# programmer.net
KiCad netlist of a schematic drawn in EAGLE
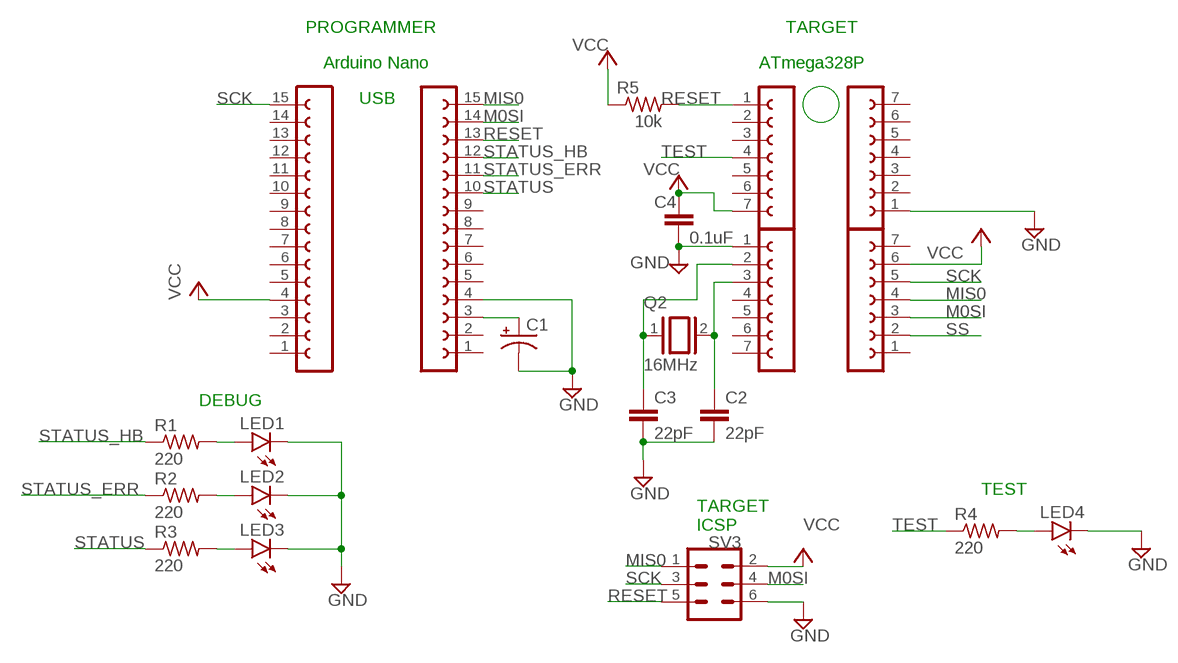
[diagram p0: schematic, sheet 1]

(export (version "E")
  (design (tool "Eeschema 10.0.6"))
  (components
    (comp (ref "C1")
      (value "CPOL-US153CLV-0405")
      (footprint "eagle-import:153CLV-0405")
      (libsource (lib "eagle-import") (part "CPOL-US153CLV-0405"))
    )
    (comp (ref "C2")
      (value "22pF")
      (footprint "eagle-import:C2.5-3")
      (libsource (lib "eagle-import") (part "C2,5-3"))
    )
    (comp (ref "C3")
      (value "22pF")
      (footprint "eagle-import:C2.5-3")
      (libsource (lib "eagle-import") (part "C2,5-3"))
    )
    (comp (ref "C4")
      (value "0.1uF")
      (footprint "eagle-import:C2.5-3")
      (libsource (lib "eagle-import") (part "C2,5-3"))
    )
    (comp (ref "LED1")
      (value "LED5MM")
      (footprint "eagle-import:LED5MM")
      (libsource (lib "eagle-import") (part "LED5MM"))
    )
    (comp (ref "LED2")
      (value "LED5MM")
      (footprint "eagle-import:LED5MM")
      (libsource (lib "eagle-import") (part "LED5MM"))
    )
    (comp (ref "LED3")
      (value "LED5MM")
      (footprint "eagle-import:LED5MM")
      (libsource (lib "eagle-import") (part "LED5MM"))
    )
    (comp (ref "LED4")
      (value "LED5MM")
      (footprint "eagle-import:LED5MM")
      (libsource (lib "eagle-import") (part "LED5MM"))
    )
    (comp (ref "Q2")
      (value "16MHz")
      (footprint "eagle-import:QS")
      (libsource (lib "eagle-import") (part "XTAL/S"))
    )
    (comp (ref "R1")
      (value "220")
      (footprint "eagle-import:0207_7")
      (libsource (lib "eagle-import") (part "R-US_0207/7"))
    )
    (comp (ref "R2")
      (value "220")
      (footprint "eagle-import:0207_7")
      (libsource (lib "eagle-import") (part "R-US_0207/7"))
    )
    (comp (ref "R3")
      (value "220")
      (footprint "eagle-import:0207_7")
      (libsource (lib "eagle-import") (part "R-US_0207/7"))
    )
    (comp (ref "R4")
      (value "220")
      (footprint "eagle-import:0207_7")
      (libsource (lib "eagle-import") (part "R-US_0207/7"))
    )
    (comp (ref "R5")
      (value "10k")
      (footprint "eagle-import:0207_7")
      (libsource (lib "eagle-import") (part "R-US_0207/7"))
    )
    (comp (ref "SV1")
      (value "FE15-1")
      (footprint "eagle-import:FE15")
      (libsource (lib "eagle-import") (part "FE15-1"))
    )
    (comp (ref "SV2")
      (value "FE15-1")
      (footprint "eagle-import:FE15")
      (libsource (lib "eagle-import") (part "FE15-1"))
    )
    (comp (ref "SV3")
      (value "MA03-2")
      (footprint "eagle-import:MA03-2")
      (libsource (lib "eagle-import") (part "MA03-2"))
    )
    (comp (ref "SV6")
      (value "FE07-1")
      (footprint "eagle-import:FE07")
      (libsource (lib "eagle-import") (part "FE07-1"))
    )
    (comp (ref "SV7")
      (value "FE07-1")
      (footprint "eagle-import:FE07")
      (libsource (lib "eagle-import") (part "FE07-1"))
    )
    (comp (ref "SV8")
      (value "FE07-1")
      (footprint "eagle-import:FE07")
      (libsource (lib "eagle-import") (part "FE07-1"))
    )
    (comp (ref "SV9")
      (value "FE07-1")
      (footprint "eagle-import:FE07")
      (libsource (lib "eagle-import") (part "FE07-1"))
    )
  )
  (nets
    (net (code "1") (name "/M0SI") (class "Default")
      (node (ref "SV1") (pin "14") (pinfunction "14_14") (pintype "passive"))
      (node (ref "SV3") (pin "4") (pinfunction "4_4") (pintype "passive"))
      (node (ref "SV9") (pin "3") (pinfunction "3_3") (pintype "passive"))
    )
    (net (code "2") (name "/MIS0") (class "Default")
      (node (ref "SV1") (pin "15") (pinfunction "15_15") (pintype "passive"))
      (node (ref "SV3") (pin "1") (pinfunction "1_1") (pintype "passive"))
      (node (ref "SV9") (pin "4") (pinfunction "4_4") (pintype "passive"))
    )
    (net (code "3") (name "/RESET") (class "Default")
      (node (ref "R5") (pin "2") (pinfunction "2_2") (pintype "passive"))
      (node (ref "SV1") (pin "13") (pinfunction "13_13") (pintype "passive"))
      (node (ref "SV3") (pin "5") (pinfunction "5_5") (pintype "passive"))
      (node (ref "SV6") (pin "1") (pinfunction "1_1") (pintype "passive"))
    )
    (net (code "4") (name "/SCK") (class "Default")
      (node (ref "SV2") (pin "15") (pinfunction "15_15") (pintype "passive"))
      (node (ref "SV3") (pin "3") (pinfunction "3_3") (pintype "passive"))
      (node (ref "SV9") (pin "5") (pinfunction "5_5") (pintype "passive"))
    )
    (net (code "5") (name "/SS") (class "Default")
      (node (ref "SV9") (pin "2") (pinfunction "2_2") (pintype "passive"))
    )
    (net (code "6") (name "/STATUS") (class "Default")
      (node (ref "R3") (pin "1") (pinfunction "1_1") (pintype "passive"))
      (node (ref "SV1") (pin "10") (pinfunction "10_10") (pintype "passive"))
    )
    (net (code "7") (name "/STATUS_ERR") (class "Default")
      (node (ref "R2") (pin "1") (pinfunction "1_1") (pintype "passive"))
      (node (ref "SV1") (pin "11") (pinfunction "11_11") (pintype "passive"))
    )
    (net (code "8") (name "/STATUS_HB") (class "Default")
      (node (ref "R1") (pin "1") (pinfunction "1_1") (pintype "passive"))
      (node (ref "SV1") (pin "12") (pinfunction "12_12") (pintype "passive"))
    )
    (net (code "9") (name "/TEST") (class "Default")
      (node (ref "R4") (pin "1") (pinfunction "1_1") (pintype "passive"))
      (node (ref "SV6") (pin "4") (pinfunction "4_4") (pintype "passive"))
    )
    (net (code "10") (name "GND") (class "Default")
      (node (ref "C1") (pin "-") (pinfunction "-_-") (pintype "passive"))
      (node (ref "C2") (pin "2") (pinfunction "2_2") (pintype "passive"))
      (node (ref "C3") (pin "2") (pinfunction "2_2") (pintype "passive"))
      (node (ref "C4") (pin "2") (pinfunction "2_2") (pintype "passive"))
      (node (ref "LED1") (pin "K") (pinfunction "C_K") (pintype "passive"))
      (node (ref "LED2") (pin "K") (pinfunction "C_K") (pintype "passive"))
      (node (ref "LED3") (pin "K") (pinfunction "C_K") (pintype "passive"))
      (node (ref "LED4") (pin "K") (pinfunction "C_K") (pintype "passive"))
      (node (ref "SV1") (pin "4") (pinfunction "4_4") (pintype "passive"))
      (node (ref "SV3") (pin "6") (pinfunction "6_6") (pintype "passive"))
      (node (ref "SV7") (pin "1") (pinfunction "1_1") (pintype "passive"))
      (node (ref "SV8") (pin "1") (pinfunction "1_1") (pintype "passive"))
    )
    (net (code "11") (name "Net-(C1-Pad+)") (class "Default")
      (node (ref "C1") (pin "+") (pinfunction "+_+") (pintype "passive"))
      (node (ref "SV1") (pin "3") (pinfunction "3_3") (pintype "passive"))
    )
    (net (code "12") (name "Net-(C2-Pad1)") (class "Default")
      (node (ref "C2") (pin "1") (pinfunction "1_1") (pintype "passive"))
      (node (ref "Q2") (pin "2") (pinfunction "2_2") (pintype "passive"))
      (node (ref "SV7") (pin "3") (pinfunction "3_3") (pintype "passive"))
    )
    (net (code "13") (name "Net-(C3-Pad1)") (class "Default")
      (node (ref "C3") (pin "1") (pinfunction "1_1") (pintype "passive"))
      (node (ref "Q2") (pin "1") (pinfunction "1_1") (pintype "passive"))
      (node (ref "SV7") (pin "2") (pinfunction "2_2") (pintype "passive"))
    )
    (net (code "14") (name "Net-(LED1-PadA)") (class "Default")
      (node (ref "LED1") (pin "A") (pinfunction "A_A") (pintype "passive"))
      (node (ref "R1") (pin "2") (pinfunction "2_2") (pintype "passive"))
    )
    (net (code "15") (name "Net-(LED2-PadA)") (class "Default")
      (node (ref "LED2") (pin "A") (pinfunction "A_A") (pintype "passive"))
      (node (ref "R2") (pin "2") (pinfunction "2_2") (pintype "passive"))
    )
    (net (code "16") (name "Net-(LED3-PadA)") (class "Default")
      (node (ref "LED3") (pin "A") (pinfunction "A_A") (pintype "passive"))
      (node (ref "R3") (pin "2") (pinfunction "2_2") (pintype "passive"))
    )
    (net (code "17") (name "Net-(LED4-PadA)") (class "Default")
      (node (ref "LED4") (pin "A") (pinfunction "A_A") (pintype "passive"))
      (node (ref "R4") (pin "2") (pinfunction "2_2") (pintype "passive"))
    )
    (net (code "18") (name "VCC") (class "Default")
      (node (ref "C4") (pin "1") (pinfunction "1_1") (pintype "passive"))
      (node (ref "R5") (pin "1") (pinfunction "1_1") (pintype "passive"))
      (node (ref "SV2") (pin "4") (pinfunction "4_4") (pintype "passive"))
      (node (ref "SV3") (pin "2") (pinfunction "2_2") (pintype "passive"))
      (node (ref "SV6") (pin "7") (pinfunction "7_7") (pintype "passive"))
      (node (ref "SV9") (pin "6") (pinfunction "6_6") (pintype "passive"))
    )
    (net (code "19") (name "unconnected-(SV1-Pad1)") (class "Default")
      (node (ref "SV1") (pin "1") (pinfunction "1_1") (pintype "passive"))
    )
    (net (code "20") (name "unconnected-(SV1-Pad2)") (class "Default")
      (node (ref "SV1") (pin "2") (pinfunction "2_2") (pintype "passive"))
    )
    (net (code "21") (name "unconnected-(SV1-Pad5)") (class "Default")
      (node (ref "SV1") (pin "5") (pinfunction "5_5") (pintype "passive"))
    )
    (net (code "22") (name "unconnected-(SV1-Pad6)") (class "Default")
      (node (ref "SV1") (pin "6") (pinfunction "6_6") (pintype "passive"))
    )
    (net (code "23") (name "unconnected-(SV1-Pad7)") (class "Default")
      (node (ref "SV1") (pin "7") (pinfunction "7_7") (pintype "passive"))
    )
    (net (code "24") (name "unconnected-(SV1-Pad8)") (class "Default")
      (node (ref "SV1") (pin "8") (pinfunction "8_8") (pintype "passive"))
    )
    (net (code "25") (name "unconnected-(SV1-Pad9)") (class "Default")
      (node (ref "SV1") (pin "9") (pinfunction "9_9") (pintype "passive"))
    )
    (net (code "26") (name "unconnected-(SV2-Pad1)") (class "Default")
      (node (ref "SV2") (pin "1") (pinfunction "1_1") (pintype "passive"))
    )
    (net (code "27") (name "unconnected-(SV2-Pad2)") (class "Default")
      (node (ref "SV2") (pin "2") (pinfunction "2_2") (pintype "passive"))
    )
    (net (code "28") (name "unconnected-(SV2-Pad3)") (class "Default")
      (node (ref "SV2") (pin "3") (pinfunction "3_3") (pintype "passive"))
    )
    (net (code "29") (name "unconnected-(SV2-Pad5)") (class "Default")
      (node (ref "SV2") (pin "5") (pinfunction "5_5") (pintype "passive"))
    )
    (net (code "30") (name "unconnected-(SV2-Pad6)") (class "Default")
      (node (ref "SV2") (pin "6") (pinfunction "6_6") (pintype "passive"))
    )
    (net (code "31") (name "unconnected-(SV2-Pad7)") (class "Default")
      (node (ref "SV2") (pin "7") (pinfunction "7_7") (pintype "passive"))
    )
    (net (code "32") (name "unconnected-(SV2-Pad8)") (class "Default")
      (node (ref "SV2") (pin "8") (pinfunction "8_8") (pintype "passive"))
    )
    (net (code "33") (name "unconnected-(SV2-Pad9)") (class "Default")
      (node (ref "SV2") (pin "9") (pinfunction "9_9") (pintype "passive"))
    )
    (net (code "34") (name "unconnected-(SV2-Pad10)") (class "Default")
      (node (ref "SV2") (pin "10") (pinfunction "10_10") (pintype "passive"))
    )
    (net (code "35") (name "unconnected-(SV2-Pad11)") (class "Default")
      (node (ref "SV2") (pin "11") (pinfunction "11_11") (pintype "passive"))
    )
    (net (code "36") (name "unconnected-(SV2-Pad12)") (class "Default")
      (node (ref "SV2") (pin "12") (pinfunction "12_12") (pintype "passive"))
    )
    (net (code "37") (name "unconnected-(SV2-Pad13)") (class "Default")
      (node (ref "SV2") (pin "13") (pinfunction "13_13") (pintype "passive"))
    )
    (net (code "38") (name "unconnected-(SV2-Pad14)") (class "Default")
      (node (ref "SV2") (pin "14") (pinfunction "14_14") (pintype "passive"))
    )
    (net (code "39") (name "unconnected-(SV6-Pad2)") (class "Default")
      (node (ref "SV6") (pin "2") (pinfunction "2_2") (pintype "passive"))
    )
    (net (code "40") (name "unconnected-(SV6-Pad3)") (class "Default")
      (node (ref "SV6") (pin "3") (pinfunction "3_3") (pintype "passive"))
    )
    (net (code "41") (name "unconnected-(SV6-Pad5)") (class "Default")
      (node (ref "SV6") (pin "5") (pinfunction "5_5") (pintype "passive"))
    )
    (net (code "42") (name "unconnected-(SV6-Pad6)") (class "Default")
      (node (ref "SV6") (pin "6") (pinfunction "6_6") (pintype "passive"))
    )
    (net (code "43") (name "unconnected-(SV7-Pad4)") (class "Default")
      (node (ref "SV7") (pin "4") (pinfunction "4_4") (pintype "passive"))
    )
    (net (code "44") (name "unconnected-(SV7-Pad5)") (class "Default")
      (node (ref "SV7") (pin "5") (pinfunction "5_5") (pintype "passive"))
    )
    (net (code "45") (name "unconnected-(SV7-Pad6)") (class "Default")
      (node (ref "SV7") (pin "6") (pinfunction "6_6") (pintype "passive"))
    )
    (net (code "46") (name "unconnected-(SV7-Pad7)") (class "Default")
      (node (ref "SV7") (pin "7") (pinfunction "7_7") (pintype "passive"))
    )
    (net (code "47") (name "unconnected-(SV8-Pad2)") (class "Default")
      (node (ref "SV8") (pin "2") (pinfunction "2_2") (pintype "passive"))
    )
    (net (code "48") (name "unconnected-(SV8-Pad3)") (class "Default")
      (node (ref "SV8") (pin "3") (pinfunction "3_3") (pintype "passive"))
    )
    (net (code "49") (name "unconnected-(SV8-Pad4)") (class "Default")
      (node (ref "SV8") (pin "4") (pinfunction "4_4") (pintype "passive"))
    )
    (net (code "50") (name "unconnected-(SV8-Pad5)") (class "Default")
      (node (ref "SV8") (pin "5") (pinfunction "5_5") (pintype "passive"))
    )
    (net (code "51") (name "unconnected-(SV8-Pad6)") (class "Default")
      (node (ref "SV8") (pin "6") (pinfunction "6_6") (pintype "passive"))
    )
    (net (code "52") (name "unconnected-(SV8-Pad7)") (class "Default")
      (node (ref "SV8") (pin "7") (pinfunction "7_7") (pintype "passive"))
    )
    (net (code "53") (name "unconnected-(SV9-Pad1)") (class "Default")
      (node (ref "SV9") (pin "1") (pinfunction "1_1") (pintype "passive"))
    )
    (net (code "54") (name "unconnected-(SV9-Pad7)") (class "Default")
      (node (ref "SV9") (pin "7") (pinfunction "7_7") (pintype "passive"))
    )
  )
)
